# BT_IMU_2_0.net
KiCad netlist of a schematic drawn in EAGLE
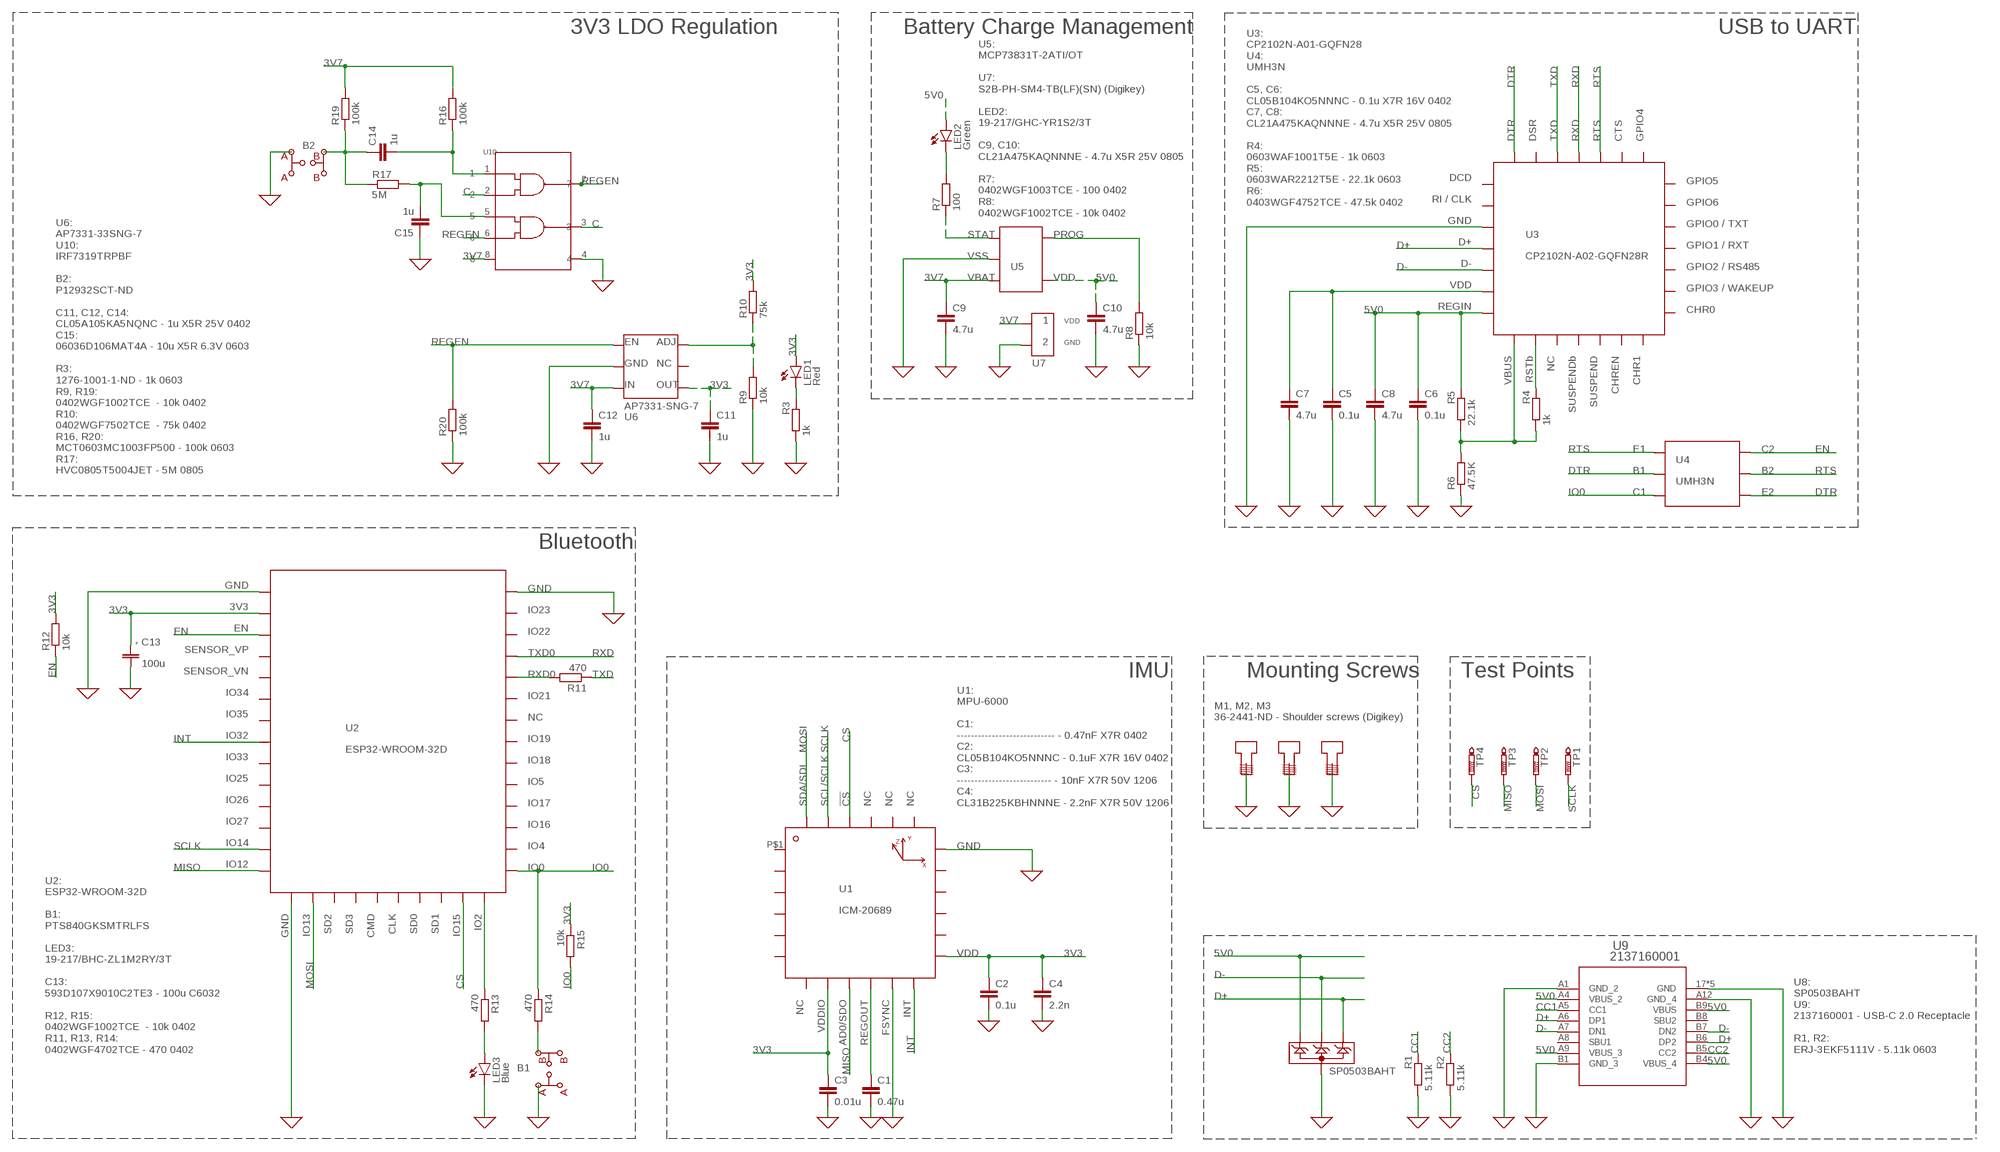
[diagram p0: schematic, sheet 1]

(export (version "E")
  (design (tool "Eeschema 10.0.6"))
  (components
    (comp (ref "B1")
      (value "P12932SCT-ND")
      (footprint "eagle-import:P12932SCT-ND")
      (libsource (lib "eagle-import") (part "P12932SCT-ND"))
    )
    (comp (ref "B2")
      (value "P12932SCT-ND")
      (footprint "eagle-import:P12932SCT-ND")
      (libsource (lib "eagle-import") (part "P12932SCT-ND"))
    )
    (comp (ref "C1")
      (value "0.47u")
      (footprint "eagle-import:C0603")
      (libsource (lib "eagle-import") (part "C-EUC0603"))
    )
    (comp (ref "C2")
      (value "0.1u")
      (footprint "eagle-import:C0402")
      (libsource (lib "eagle-import") (part "C-EUC0402"))
    )
    (comp (ref "C3")
      (value "0.01u")
      (footprint "eagle-import:C0402")
      (libsource (lib "eagle-import") (part "C-EUC0402"))
    )
    (comp (ref "C4")
      (value "2.2n")
      (footprint "eagle-import:C1206")
      (libsource (lib "eagle-import") (part "C-EUC1206"))
    )
    (comp (ref "C5")
      (value "0.1u")
      (footprint "eagle-import:C0402")
      (libsource (lib "eagle-import") (part "C-EUC0402"))
    )
    (comp (ref "C6")
      (value "0.1u")
      (footprint "eagle-import:C0402")
      (libsource (lib "eagle-import") (part "C-EUC0402"))
    )
    (comp (ref "C7")
      (value "4.7u")
      (footprint "eagle-import:C0805")
      (libsource (lib "eagle-import") (part "C-EUC0805"))
    )
    (comp (ref "C8")
      (value "4.7u")
      (footprint "eagle-import:C0805")
      (libsource (lib "eagle-import") (part "C-EUC0805"))
    )
    (comp (ref "C9")
      (value "4.7u")
      (footprint "eagle-import:C0805")
      (libsource (lib "eagle-import") (part "C-EUC0805"))
    )
    (comp (ref "C10")
      (value "4.7u")
      (footprint "eagle-import:C0805")
      (libsource (lib "eagle-import") (part "C-EUC0805"))
    )
    (comp (ref "C11")
      (value "1u")
      (footprint "eagle-import:C0402")
      (libsource (lib "eagle-import") (part "C-EUC0402"))
    )
    (comp (ref "C12")
      (value "1u")
      (footprint "eagle-import:C0402")
      (libsource (lib "eagle-import") (part "C-EUC0402"))
    )
    (comp (ref "C13")
      (value "100u")
      (footprint "eagle-import:C6032")
      (libsource (lib "eagle-import") (part "593D107X9010C2TE3"))
    )
    (comp (ref "C14")
      (value "1u")
      (footprint "eagle-import:C0402")
      (libsource (lib "eagle-import") (part "C-EUC0402"))
    )
    (comp (ref "C15")
      (value "1u")
      (footprint "eagle-import:C0603")
      (libsource (lib "eagle-import") (part "C-EUC0603"))
    )
    (comp (ref "LED1")
      (value "Red")
      (footprint "eagle-import:CHIP-LED0603")
      (libsource (lib "eagle-import") (part "LEDCHIP-LED0603"))
    )
    (comp (ref "LED2")
      (value "Green")
      (footprint "eagle-import:SML0603")
      (libsource (lib "eagle-import") (part "LEDSML0603"))
    )
    (comp (ref "LED3")
      (value "Blue")
      (footprint "eagle-import:SML0603")
      (libsource (lib "eagle-import") (part "LEDSML0603"))
    )
    (comp (ref "M1")
      (value "2441")
      (footprint "eagle-import:2441")
      (libsource (lib "eagle-import") (part "2441"))
    )
    (comp (ref "M2")
      (value "2441")
      (footprint "eagle-import:2441")
      (libsource (lib "eagle-import") (part "2441"))
    )
    (comp (ref "M3")
      (value "2441")
      (footprint "eagle-import:2441")
      (libsource (lib "eagle-import") (part "2441"))
    )
    (comp (ref "R1")
      (value "5.11k")
      (footprint "eagle-import:R0603")
      (libsource (lib "eagle-import") (part "R-EU_R0603"))
    )
    (comp (ref "R2")
      (value "5.11k")
      (footprint "eagle-import:R0603")
      (libsource (lib "eagle-import") (part "R-EU_R0603"))
    )
    (comp (ref "R3")
      (value "1k")
      (footprint "eagle-import:R0603")
      (libsource (lib "eagle-import") (part "R-EU_R0603"))
    )
    (comp (ref "R4")
      (value "1k")
      (footprint "eagle-import:R0603")
      (libsource (lib "eagle-import") (part "R-EU_R0603"))
    )
    (comp (ref "R5")
      (value "22.1k")
      (footprint "eagle-import:R0603")
      (libsource (lib "eagle-import") (part "R-EU_R0603"))
    )
    (comp (ref "R6")
      (value "47.5K")
      (footprint "eagle-import:R0402")
      (libsource (lib "eagle-import") (part "R-EU_R0402"))
    )
    (comp (ref "R7")
      (value "100")
      (footprint "eagle-import:R0402")
      (libsource (lib "eagle-import") (part "R-EU_R0402"))
    )
    (comp (ref "R8")
      (value "10k")
      (footprint "eagle-import:R0402")
      (libsource (lib "eagle-import") (part "R-EU_R0402"))
    )
    (comp (ref "R9")
      (value "10k")
      (footprint "eagle-import:R0402")
      (libsource (lib "eagle-import") (part "R-EU_R0402"))
    )
    (comp (ref "R10")
      (value "75k")
      (footprint "eagle-import:R0402")
      (libsource (lib "eagle-import") (part "R-EU_R0402"))
    )
    (comp (ref "R11")
      (value "470")
      (footprint "eagle-import:R0402")
      (libsource (lib "eagle-import") (part "R-EU_R0402"))
    )
    (comp (ref "R12")
      (value "10k")
      (footprint "eagle-import:R0402")
      (libsource (lib "eagle-import") (part "R-EU_R0402"))
    )
    (comp (ref "R13")
      (value "470")
      (footprint "eagle-import:R0402")
      (libsource (lib "eagle-import") (part "R-EU_R0402"))
    )
    (comp (ref "R14")
      (value "470")
      (footprint "eagle-import:R0402")
      (libsource (lib "eagle-import") (part "R-EU_R0402"))
    )
    (comp (ref "R15")
      (value "10k")
      (footprint "eagle-import:R0402")
      (libsource (lib "eagle-import") (part "R-EU_R0402"))
    )
    (comp (ref "R16")
      (value "100k")
      (footprint "eagle-import:R0603")
      (libsource (lib "eagle-import") (part "R-EU_R0603"))
    )
    (comp (ref "R17")
      (value "5M")
      (footprint "eagle-import:R0805")
      (libsource (lib "eagle-import") (part "R-EU_R0805"))
    )
    (comp (ref "R19")
      (value "100k")
      (footprint "eagle-import:R0603")
      (libsource (lib "eagle-import") (part "R-EU_R0603"))
    )
    (comp (ref "R20")
      (value "100k")
      (footprint "eagle-import:R0603")
      (libsource (lib "eagle-import") (part "R-EU_R0603"))
    )
    (comp (ref "TP1")
      (value "PTR1B1,27")
      (footprint "eagle-import:B1,27")
      (libsource (lib "eagle-import") (part "PTR1B1,27"))
    )
    (comp (ref "TP2")
      (value "PTR1B1,27")
      (footprint "eagle-import:B1,27")
      (libsource (lib "eagle-import") (part "PTR1B1,27"))
    )
    (comp (ref "TP3")
      (value "PTR1B1,27")
      (footprint "eagle-import:B1,27")
      (libsource (lib "eagle-import") (part "PTR1B1,27"))
    )
    (comp (ref "TP4")
      (value "PTR1B1,27")
      (footprint "eagle-import:B1,27")
      (libsource (lib "eagle-import") (part "PTR1B1,27"))
    )
    (comp (ref "U1")
      (value "ICM-20689")
      (footprint "eagle-import:24-QFN(4X4)")
      (libsource (lib "eagle-import") (part "ICM-20689"))
    )
    (comp (ref "U2")
      (value "ESP32-WROOM-32D")
      (footprint "eagle-import:ESP32-WROOM-32D")
      (libsource (lib "eagle-import") (part "ESP32-WROOM-32D"))
    )
    (comp (ref "U3")
      (value "CP2102N-A02-GQFN28R")
      (footprint "eagle-import:28-QFN(5X5)")
      (libsource (lib "eagle-import") (part "CP2102N-A02-GQFN28R"))
    )
    (comp (ref "U4")
      (value "UMH3N")
      (footprint "eagle-import:UMT6")
      (libsource (lib "eagle-import") (part "UMH3N"))
    )
    (comp (ref "U5")
      (value "MCP73831T-2ATI/OT")
      (footprint "eagle-import:SOT-23-5")
      (libsource (lib "eagle-import") (part "MCP73831T-2ATI/OT"))
    )
    (comp (ref "U6")
      (value "AP7331-SNG-7")
      (footprint "eagle-import:U-DFN2020-6")
      (libsource (lib "eagle-import") (part "AP7331-SNG-7"))
    )
    (comp (ref "U7")
      (value "S2B-PH-SM4-TB(LF)(SN)")
      (footprint "eagle-import:S2B-PH-SM4-TB(LF)(SN)")
      (libsource (lib "eagle-import") (part "S2B-PH-SM4-TB(LF)(SN)"))
    )
    (comp (ref "U8")
      (value "SP0503BAHT")
      (footprint "eagle-import:SOT-143-4")
      (libsource (lib "eagle-import") (part "SP0503BAHT"))
    )
    (comp (ref "U9")
      (value "2137160001")
      (footprint "eagle-import:2137160001_MOL")
      (fields (field (name "COPYRIGHT") "Copyright (C) 2018 Accelerated Designs. All rights reserved"))
      (libsource (lib "eagle-import") (part "2137160001"))
    )
    (comp (ref "U10")
      (value "TC7WZ00FKSOT-765")
      (footprint "eagle-import:SOT-765")
      (libsource (lib "eagle-import") (part "TC7WZ00FKSOT-765"))
    )
  )
  (nets
    (net (code "1") (name "/3V3") (class "Default")
      (node (ref "C11") (pin "1") (pinfunction "1_1") (pintype "passive"))
      (node (ref "C13") (pin "P$1") (pinfunction "P$1_P$1") (pintype "bidirectional"))
      (node (ref "C2") (pin "1") (pinfunction "1_1") (pintype "passive"))
      (node (ref "C3") (pin "1") (pinfunction "1_1") (pintype "passive"))
      (node (ref "C4") (pin "1") (pinfunction "1_1") (pintype "passive"))
      (node (ref "LED1") (pin "A") (pinfunction "A_A") (pintype "passive"))
      (node (ref "R10") (pin "2") (pinfunction "2_2") (pintype "passive"))
      (node (ref "R12") (pin "2") (pinfunction "2_2") (pintype "passive"))
      (node (ref "R15") (pin "1") (pinfunction "1_1") (pintype "passive"))
      (node (ref "U1") (pin "P$13") (pinfunction "P$13_P$13") (pintype "power_in"))
      (node (ref "U1") (pin "P$8") (pinfunction "P$8_P$8") (pintype "power_in"))
      (node (ref "U2") (pin "P$2") (pinfunction "P$2_P$2") (pintype "input"))
      (node (ref "U6") (pin "P$4") (pinfunction "P$4_P$4") (pintype "output"))
    )
    (net (code "2") (name "/3V7") (class "Default")
      (node (ref "C12") (pin "1") (pinfunction "1_1") (pintype "passive"))
      (node (ref "C9") (pin "1") (pinfunction "1_1") (pintype "passive"))
      (node (ref "R16") (pin "2") (pinfunction "2_2") (pintype "passive"))
      (node (ref "R19") (pin "2") (pinfunction "2_2") (pintype "passive"))
      (node (ref "U10") (pin "8") (pinfunction "8_8") (pintype "passive"))
      (node (ref "U5") (pin "P$3") (pinfunction "P$3_P$3") (pintype "power_in"))
      (node (ref "U6") (pin "P$3") (pinfunction "P$3_P$3") (pintype "input"))
      (node (ref "U7") (pin "P$1") (pinfunction "P$1_P$1") (pintype "bidirectional"))
    )
    (net (code "3") (name "/5V0") (class "Default")
      (node (ref "C10") (pin "1") (pinfunction "1_1") (pintype "passive"))
      (node (ref "C6") (pin "1") (pinfunction "1_1") (pintype "passive"))
      (node (ref "C8") (pin "1") (pinfunction "1_1") (pintype "passive"))
      (node (ref "LED2") (pin "A") (pinfunction "A_A") (pintype "passive"))
      (node (ref "R5") (pin "2") (pinfunction "2_2") (pintype "passive"))
      (node (ref "U3") (pin "P$6") (pinfunction "P$7_P$6") (pintype "power_in"))
      (node (ref "U5") (pin "P$4") (pinfunction "P$4_P$4") (pintype "power_in"))
      (node (ref "U8") (pin "P$2") (pinfunction "P$2_P$2") (pintype "bidirectional"))
      (node (ref "U9") (pin "A4") (pinfunction "VBUS_2_A4") (pintype "power_in"))
      (node (ref "U9") (pin "A9") (pinfunction "VBUS_3_A9") (pintype "power_in"))
      (node (ref "U9") (pin "B4") (pinfunction "VBUS_4_B4") (pintype "power_in"))
      (node (ref "U9") (pin "B9") (pinfunction "VBUS_B9") (pintype "power_in"))
    )
    (net (code "4") (name "/C") (class "Default")
      (node (ref "U10") (pin "2") (pinfunction "2_2") (pintype "passive"))
      (node (ref "U10") (pin "3") (pinfunction "3_3") (pintype "passive"))
    )
    (net (code "5") (name "/CC1") (class "Default")
      (node (ref "R1") (pin "2") (pinfunction "2_2") (pintype "passive"))
      (node (ref "U9") (pin "A5") (pinfunction "CC1_A5") (pintype "bidirectional"))
    )
    (net (code "6") (name "/CC2") (class "Default")
      (node (ref "R2") (pin "2") (pinfunction "2_2") (pintype "passive"))
      (node (ref "U9") (pin "B5") (pinfunction "CC2_B5") (pintype "bidirectional"))
    )
    (net (code "7") (name "/CS") (class "Default")
      (node (ref "TP4") (pin "TP") (pinfunction "TP_TP") (pintype "input"))
      (node (ref "U1") (pin "P$22") (pinfunction "P$22_P$22") (pintype "input"))
      (node (ref "U2") (pin "P$23") (pinfunction "P$23_P$23") (pintype "input"))
    )
    (net (code "8") (name "/D+") (class "Default")
      (node (ref "U3") (pin "P$3") (pinfunction "P$4_P$3") (pintype "bidirectional"))
      (node (ref "U8") (pin "P$4") (pinfunction "P$4_P$4") (pintype "bidirectional"))
      (node (ref "U9") (pin "A6") (pinfunction "DP1_A6") (pintype "bidirectional"))
      (node (ref "U9") (pin "B6") (pinfunction "DP2_B6") (pintype "bidirectional"))
    )
    (net (code "9") (name "/D-") (class "Default")
      (node (ref "U3") (pin "P$4") (pinfunction "P$5_P$4") (pintype "bidirectional"))
      (node (ref "U8") (pin "P$3") (pinfunction "P$3_P$3") (pintype "bidirectional"))
      (node (ref "U9") (pin "A7") (pinfunction "DN1_A7") (pintype "bidirectional"))
      (node (ref "U9") (pin "B7") (pinfunction "DN2_B7") (pintype "bidirectional"))
    )
    (net (code "10") (name "/DTR") (class "Default")
      (node (ref "U3") (pin "P$27") (pinfunction "P$28_P$27") (pintype "output"))
      (node (ref "U4") (pin "P$2") (pinfunction "P$2_P$2") (pintype "bidirectional"))
      (node (ref "U4") (pin "P$4") (pinfunction "P$4_P$4") (pintype "bidirectional"))
    )
    (net (code "11") (name "/EN") (class "Default")
      (node (ref "R12") (pin "1") (pinfunction "1_1") (pintype "passive"))
      (node (ref "U2") (pin "P$3") (pinfunction "P$3_P$3") (pintype "input"))
      (node (ref "U4") (pin "P$6") (pinfunction "P$6_P$6") (pintype "bidirectional"))
    )
    (net (code "12") (name "/INT") (class "Default")
      (node (ref "U1") (pin "P$12") (pinfunction "P$12_P$12") (pintype "output"))
      (node (ref "U2") (pin "P$8") (pinfunction "P$8_P$8") (pintype "input"))
    )
    (net (code "13") (name "/IO0") (class "Default")
      (node (ref "R14") (pin "1") (pinfunction "1_1") (pintype "passive"))
      (node (ref "R15") (pin "2") (pinfunction "2_2") (pintype "passive"))
      (node (ref "U2") (pin "P$25") (pinfunction "P$25_P$25") (pintype "input"))
      (node (ref "U4") (pin "P$3") (pinfunction "P$3_P$3") (pintype "bidirectional"))
    )
    (net (code "14") (name "/MISO") (class "Default")
      (node (ref "TP3") (pin "TP") (pinfunction "TP_TP") (pintype "input"))
      (node (ref "U1") (pin "P$9") (pinfunction "P$9_P$9") (pintype "input"))
      (node (ref "U2") (pin "P$14") (pinfunction "P$14_P$14") (pintype "input"))
    )
    (net (code "15") (name "/MOSI") (class "Default")
      (node (ref "TP2") (pin "TP") (pinfunction "TP_TP") (pintype "input"))
      (node (ref "U1") (pin "P$24") (pinfunction "P$24_P$24") (pintype "bidirectional"))
      (node (ref "U2") (pin "P$16") (pinfunction "P$16_P$16") (pintype "input"))
    )
    (net (code "16") (name "/REGEN") (class "Default")
      (node (ref "R20") (pin "2") (pinfunction "2_2") (pintype "passive"))
      (node (ref "U10") (pin "6") (pinfunction "6_6") (pintype "passive"))
      (node (ref "U10") (pin "7") (pinfunction "7_7") (pintype "passive"))
      (node (ref "U6") (pin "P$1") (pinfunction "P$1_P$1") (pintype "input"))
    )
    (net (code "17") (name "/RTS") (class "Default")
      (node (ref "U3") (pin "P$23") (pinfunction "P$24_P$23") (pintype "output"))
      (node (ref "U4") (pin "P$1") (pinfunction "P$1_P$1") (pintype "bidirectional"))
      (node (ref "U4") (pin "P$5") (pinfunction "P$5_P$5") (pintype "bidirectional"))
    )
    (net (code "18") (name "/RXD") (class "Default")
      (node (ref "U2") (pin "P$35") (pinfunction "P$35_P$35") (pintype "input"))
      (node (ref "U3") (pin "P$24") (pinfunction "P$25_P$24") (pintype "input"))
    )
    (net (code "19") (name "/SCLK") (class "Default")
      (node (ref "TP1") (pin "TP") (pinfunction "TP_TP") (pintype "input"))
      (node (ref "U1") (pin "P$23") (pinfunction "P$23_P$23") (pintype "input"))
      (node (ref "U2") (pin "P$13") (pinfunction "P$13_P$13") (pintype "input"))
    )
    (net (code "20") (name "/TXD") (class "Default")
      (node (ref "R11") (pin "1") (pinfunction "1_1") (pintype "passive"))
      (node (ref "U3") (pin "P$25") (pinfunction "P$26_P$25") (pintype "output"))
    )
    (net (code "21") (name "GND") (class "Default")
      (node (ref "B1") (pin "P$2") (pinfunction "P$2_P$2") (pintype "bidirectional"))
      (node (ref "B2") (pin "P$2") (pinfunction "P$2_P$2") (pintype "bidirectional"))
      (node (ref "C1") (pin "2") (pinfunction "2_2") (pintype "passive"))
      (node (ref "C10") (pin "2") (pinfunction "2_2") (pintype "passive"))
      (node (ref "C11") (pin "2") (pinfunction "2_2") (pintype "passive"))
      (node (ref "C12") (pin "2") (pinfunction "2_2") (pintype "passive"))
      (node (ref "C13") (pin "P$2") (pinfunction "P$2_P$2") (pintype "bidirectional"))
      (node (ref "C15") (pin "1") (pinfunction "1_1") (pintype "passive"))
      (node (ref "C2") (pin "2") (pinfunction "2_2") (pintype "passive"))
      (node (ref "C3") (pin "2") (pinfunction "2_2") (pintype "passive"))
      (node (ref "C4") (pin "2") (pinfunction "2_2") (pintype "passive"))
      (node (ref "C5") (pin "2") (pinfunction "2_2") (pintype "passive"))
      (node (ref "C6") (pin "2") (pinfunction "2_2") (pintype "passive"))
      (node (ref "C7") (pin "2") (pinfunction "2_2") (pintype "passive"))
      (node (ref "C8") (pin "2") (pinfunction "2_2") (pintype "passive"))
      (node (ref "C9") (pin "2") (pinfunction "2_2") (pintype "passive"))
      (node (ref "LED3") (pin "C") (pinfunction "C_C") (pintype "passive"))
      (node (ref "M1") (pin "P$1") (pinfunction "P$1_P$1") (pintype "power_in"))
      (node (ref "M2") (pin "P$1") (pinfunction "P$1_P$1") (pintype "power_in"))
      (node (ref "M3") (pin "P$1") (pinfunction "P$1_P$1") (pintype "power_in"))
      (node (ref "R1") (pin "1") (pinfunction "1_1") (pintype "passive"))
      (node (ref "R2") (pin "1") (pinfunction "1_1") (pintype "passive"))
      (node (ref "R20") (pin "1") (pinfunction "1_1") (pintype "passive"))
      (node (ref "R3") (pin "1") (pinfunction "1_1") (pintype "passive"))
      (node (ref "R6") (pin "1") (pinfunction "1_1") (pintype "passive"))
      (node (ref "R8") (pin "1") (pinfunction "1_1") (pintype "passive"))
      (node (ref "R9") (pin "1") (pinfunction "1_1") (pintype "passive"))
      (node (ref "U1") (pin "P$11") (pinfunction "P$11_P$11") (pintype "input"))
      (node (ref "U1") (pin "P$18") (pinfunction "P$18_P$18") (pintype "power_in"))
      (node (ref "U10") (pin "4") (pinfunction "4_4") (pintype "passive"))
      (node (ref "U2") (pin "P$1") (pinfunction "P$1_P$1") (pintype "input"))
      (node (ref "U2") (pin "P$15") (pinfunction "P$15_P$15") (pintype "input"))
      (node (ref "U2") (pin "P$38") (pinfunction "P$38_P$38") (pintype "input"))
      (node (ref "U2") (pin "P$39") (pinfunction "P$1_P$39") (pintype "input"))
      (node (ref "U2") (pin "P$40") (pinfunction "P$1_P$40") (pintype "input"))
      (node (ref "U2") (pin "P$41") (pinfunction "P$1_P$41") (pintype "input"))
      (node (ref "U2") (pin "P$42") (pinfunction "P$1_P$42") (pintype "input"))
      (node (ref "U2") (pin "P$43") (pinfunction "P$1_P$43") (pintype "input"))
      (node (ref "U2") (pin "P$44") (pinfunction "P$1_P$44") (pintype "input"))
      (node (ref "U2") (pin "P$45") (pinfunction "P$1_P$45") (pintype "input"))
      (node (ref "U2") (pin "P$46") (pinfunction "P$1_P$46") (pintype "input"))
      (node (ref "U2") (pin "P$47") (pinfunction "P$1_P$47") (pintype "input"))
      (node (ref "U3") (pin "P$2") (pinfunction "P$3_P$2") (pintype "power_in"))
      (node (ref "U3") (pin "P$28") (pinfunction "P$3_P$28") (pintype "power_in"))
      (node (ref "U3") (pin "P$29") (pinfunction "P$3_P$29") (pintype "power_in"))
      (node (ref "U3") (pin "P$30") (pinfunction "P$3_P$30") (pintype "power_in"))
      (node (ref "U3") (pin "P$31") (pinfunction "P$3_P$31") (pintype "power_in"))
      (node (ref "U3") (pin "P$32") (pinfunction "P$3_P$32") (pintype "power_in"))
      (node (ref "U3") (pin "P$33") (pinfunction "P$3_P$33") (pintype "power_in"))
      (node (ref "U3") (pin "P$34") (pinfunction "P$3_P$34") (pintype "power_in"))
      (node (ref "U3") (pin "P$35") (pinfunction "P$3_P$35") (pintype "power_in"))
      (node (ref "U3") (pin "P$36") (pinfunction "P$3_P$36") (pintype "power_in"))
      (node (ref "U5") (pin "P$2") (pinfunction "P$2_P$2") (pintype "power_in"))
      (node (ref "U6") (pin "P$2") (pinfunction "P$2_P$2") (pintype "power_in"))
      (node (ref "U6") (pin "P$7") (pinfunction "P$2_P$7") (pintype "power_in"))
      (node (ref "U6") (pin "P$8") (pinfunction "P$2_P$8") (pintype "power_in"))
      (node (ref "U7") (pin "P$2") (pinfunction "P$2_P$2") (pintype "bidirectional"))
      (node (ref "U8") (pin "P$1") (pinfunction "P$1_P$1") (pintype "bidirectional"))
      (node (ref "U9") (pin "17") (pinfunction "GND_17") (pintype "passive"))
      (node (ref "U9") (pin "18") (pinfunction "GND_18") (pintype "passive"))
      (node (ref "U9") (pin "19") (pinfunction "GND_19") (pintype "passive"))
      (node (ref "U9") (pin "20") (pinfunction "GND_20") (pintype "passive"))
      (node (ref "U9") (pin "A1") (pinfunction "GND_2_A1") (pintype "passive"))
      (node (ref "U9") (pin "A12") (pinfunction "GND_4_A12") (pintype "passive"))
      (node (ref "U9") (pin "B1") (pinfunction "GND_3_B1") (pintype "passive"))
      (node (ref "U9") (pin "B12") (pinfunction "GND_B12") (pintype "passive"))
    )
    (net (code "22") (name "Net-(B1-PadP$4)") (class "Default")
      (node (ref "B1") (pin "P$4") (pinfunction "P$4_P$4") (pintype "bidirectional"))
      (node (ref "R14") (pin "2") (pinfunction "2_2") (pintype "passive"))
    )
    (net (code "23") (name "Net-(B2-PadP$4)") (class "Default")
      (node (ref "B2") (pin "P$4") (pinfunction "P$4_P$4") (pintype "bidirectional"))
      (node (ref "C14") (pin "1") (pinfunction "1_1") (pintype "passive"))
      (node (ref "R17") (pin "1") (pinfunction "1_1") (pintype "passive"))
      (node (ref "R19") (pin "1") (pinfunction "1_1") (pintype "passive"))
    )
    (net (code "24") (name "Net-(C1-Pad1)") (class "Default")
      (node (ref "C1") (pin "1") (pinfunction "1_1") (pintype "passive"))
      (node (ref "U1") (pin "P$10") (pinfunction "P$10_P$10") (pintype "power_in"))
    )
    (net (code "25") (name "Net-(C14-Pad2)") (class "Default")
      (node (ref "C14") (pin "2") (pinfunction "2_2") (pintype "passive"))
      (node (ref "R16") (pin "1") (pinfunction "1_1") (pintype "passive"))
      (node (ref "U10") (pin "1") (pinfunction "1_1") (pintype "passive"))
    )
    (net (code "26") (name "Net-(C15-Pad2)") (class "Default")
      (node (ref "C15") (pin "2") (pinfunction "2_2") (pintype "passive"))
      (node (ref "R17") (pin "2") (pinfunction "2_2") (pintype "passive"))
      (node (ref "U10") (pin "5") (pinfunction "5_5") (pintype "passive"))
    )
    (net (code "27") (name "Net-(LED1-PadC)") (class "Default")
      (node (ref "LED1") (pin "C") (pinfunction "C_C") (pintype "passive"))
      (node (ref "R3") (pin "2") (pinfunction "2_2") (pintype "passive"))
    )
    (net (code "28") (name "Net-(LED2-PadC)") (class "Default")
      (node (ref "LED2") (pin "C") (pinfunction "C_C") (pintype "passive"))
      (node (ref "R7") (pin "2") (pinfunction "2_2") (pintype "passive"))
    )
    (net (code "29") (name "Net-(LED3-PadA)") (class "Default")
      (node (ref "LED3") (pin "A") (pinfunction "A_A") (pintype "passive"))
      (node (ref "R13") (pin "2") (pinfunction "2_2") (pintype "passive"))
    )
    (net (code "30") (name "Net-(R7-Pad1)") (class "Default")
      (node (ref "R7") (pin "1") (pinfunction "1_1") (pintype "passive"))
      (node (ref "U5") (pin "P$1") (pinfunction "P$1_P$1") (pintype "bidirectional"))
    )
    (net (code "31") (name "Net-(R8-Pad2)") (class "Default")
      (node (ref "R8") (pin "2") (pinfunction "2_2") (pintype "passive"))
      (node (ref "U5") (pin "P$5") (pinfunction "P$5_P$5") (pintype "input"))
    )
    (net (code "32") (name "Net-(R10-Pad1)") (class "Default")
      (node (ref "R10") (pin "1") (pinfunction "1_1") (pintype "passive"))
      (node (ref "R9") (pin "2") (pinfunction "2_2") (pintype "passive"))
      (node (ref "U6") (pin "P$6") (pinfunction "P$6_P$6") (pintype "input"))
    )
    (net (code "33") (name "Net-(R11-Pad2)") (class "Default")
      (node (ref "R11") (pin "2") (pinfunction "2_2") (pintype "passive"))
      (node (ref "U2") (pin "P$34") (pinfunction "P$34_P$34") (pintype "input"))
    )
    (net (code "34") (name "Net-(R13-Pad1)") (class "Default")
      (node (ref "R13") (pin "1") (pinfunction "1_1") (pintype "passive"))
      (node (ref "U2") (pin "P$24") (pinfunction "P$24_P$24") (pintype "input"))
    )
    (net (code "35") (name "Net-(U3-P$6)") (class "Default")
      (node (ref "C5") (pin "1") (pinfunction "1_1") (pintype "passive"))
      (node (ref "C7") (pin "1") (pinfunction "1_1") (pintype "passive"))
      (node (ref "U3") (pin "P$5") (pinfunction "P$6_P$5") (pintype "power_in"))
    )
    (net (code "36") (name "Net-(U3-P$8)") (class "Default")
      (node (ref "R4") (pin "1") (pinfunction "1_1") (pintype "passive"))
      (node (ref "R5") (pin "1") (pinfunction "1_1") (pintype "passive"))
      (node (ref "R6") (pin "2") (pinfunction "2_2") (pintype "passive"))
      (node (ref "U3") (pin "P$7") (pinfunction "P$8_P$7") (pintype "input"))
    )
    (net (code "37") (name "Net-(U3-P$9)") (class "Default")
      (node (ref "R4") (pin "2") (pinfunction "2_2") (pintype "passive"))
      (node (ref "U3") (pin "P$8") (pinfunction "P$9_P$8") (pintype "input"))
    )
    (net (code "38") (name "unconnected-(B1-PadP$1)") (class "Default")
      (node (ref "B1") (pin "P$1") (pinfunction "P$1_P$1") (pintype "bidirectional"))
    )
    (net (code "39") (name "unconnected-(B1-PadP$3)") (class "Default")
      (node (ref "B1") (pin "P$3") (pinfunction "P$3_P$3") (pintype "bidirectional"))
    )
    (net (code "40") (name "unconnected-(B2-PadP$1)") (class "Default")
      (node (ref "B2") (pin "P$1") (pinfunction "P$1_P$1") (pintype "bidirectional"))
    )
    (net (code "41") (name "unconnected-(B2-PadP$3)") (class "Default")
      (node (ref "B2") (pin "P$3") (pinfunction "P$3_P$3") (pintype "bidirectional"))
    )
    (net (code "42") (name "unconnected-(U1-PadP$1)") (class "Default")
      (node (ref "U1") (pin "P$1") (pinfunction "P$1_P$1") (pintype "no_connect"))
    )
    (net (code "43") (name "unconnected-(U1-PadP$2)") (class "Default")
      (node (ref "U1") (pin "P$2") (pinfunction "P$2_P$2") (pintype "no_connect"))
    )
    (net (code "44") (name "unconnected-(U1-PadP$3)") (class "Default")
      (node (ref "U1") (pin "P$3") (pinfunction "P$3_P$3") (pintype "no_connect"))
    )
    (net (code "45") (name "unconnected-(U1-PadP$4)") (class "Default")
      (node (ref "U1") (pin "P$4") (pinfunction "P$4_P$4") (pintype "no_connect"))
    )
    (net (code "46") (name "unconnected-(U1-PadP$5)") (class "Default")
      (node (ref "U1") (pin "P$5") (pinfunction "P$5_P$5") (pintype "no_connect"))
    )
    (net (code "47") (name "unconnected-(U1-PadP$6)") (class "Default")
      (node (ref "U1") (pin "P$6") (pinfunction "P$6_P$6") (pintype "no_connect"))
    )
    (net (code "48") (name "unconnected-(U1-PadP$7)") (class "Default")
      (node (ref "U1") (pin "P$7") (pinfunction "P$7_P$7") (pintype "no_connect"))
    )
    (net (code "49") (name "unconnected-(U1-PadP$14)") (class "Default")
      (node (ref "U1") (pin "P$14") (pinfunction "P$14_P$14") (pintype "no_connect"))
    )
    (net (code "50") (name "unconnected-(U1-PadP$15)") (class "Default")
      (node (ref "U1") (pin "P$15") (pinfunction "P$15_P$15") (pintype "no_connect"))
    )
    (net (code "51") (name "unconnected-(U1-PadP$16)") (class "Default")
      (node (ref "U1") (pin "P$16") (pinfunction "P$16_P$16") (pintype "no_connect"))
    )
    (net (code "52") (name "unconnected-(U1-PadP$17)") (class "Default")
      (node (ref "U1") (pin "P$17") (pinfunction "P$17_P$17") (pintype "no_connect"))
    )
    (net (code "53") (name "unconnected-(U1-PadP$19)") (class "Default")
      (node (ref "U1") (pin "P$19") (pinfunction "P$19_P$19") (pintype "no_connect"))
    )
    (net (code "54") (name "unconnected-(U1-PadP$20)") (class "Default")
      (node (ref "U1") (pin "P$20") (pinfunction "P$20_P$20") (pintype "no_connect"))
    )
    (net (code "55") (name "unconnected-(U1-PadP$21)") (class "Default")
      (node (ref "U1") (pin "P$21") (pinfunction "P$21_P$21") (pintype "no_connect"))
    )
    (net (code "56") (name "unconnected-(U2-PadP$4)") (class "Default")
      (node (ref "U2") (pin "P$4") (pinfunction "P$4_P$4") (pintype "input"))
    )
    (net (code "57") (name "unconnected-(U2-PadP$5)") (class "Default")
      (node (ref "U2") (pin "P$5") (pinfunction "P$5_P$5") (pintype "input"))
    )
    (net (code "58") (name "unconnected-(U2-PadP$6)") (class "Default")
      (node (ref "U2") (pin "P$6") (pinfunction "P$6_P$6") (pintype "input"))
    )
    (net (code "59") (name "unconnected-(U2-PadP$7)") (class "Default")
      (node (ref "U2") (pin "P$7") (pinfunction "P$7_P$7") (pintype "input"))
    )
    (net (code "60") (name "unconnected-(U2-PadP$9)") (class "Default")
      (node (ref "U2") (pin "P$9") (pinfunction "P$9_P$9") (pintype "input"))
    )
    (net (code "61") (name "unconnected-(U2-PadP$10)") (class "Default")
      (node (ref "U2") (pin "P$10") (pinfunction "P$10_P$10") (pintype "input"))
    )
    (net (code "62") (name "unconnected-(U2-PadP$11)") (class "Default")
      (node (ref "U2") (pin "P$11") (pinfunction "P$11_P$11") (pintype "input"))
    )
    (net (code "63") (name "unconnected-(U2-PadP$12)") (class "Default")
      (node (ref "U2") (pin "P$12") (pinfunction "P$12_P$12") (pintype "input"))
    )
    (net (code "64") (name "unconnected-(U2-PadP$17)") (class "Default")
      (node (ref "U2") (pin "P$17") (pinfunction "P$17_P$17") (pintype "input"))
    )
    (net (code "65") (name "unconnected-(U2-PadP$18)") (class "Default")
      (node (ref "U2") (pin "P$18") (pinfunction "P$18_P$18") (pintype "input"))
    )
    (net (code "66") (name "unconnected-(U2-PadP$19)") (class "Default")
      (node (ref "U2") (pin "P$19") (pinfunction "P$19_P$19") (pintype "input"))
    )
    (net (code "67") (name "unconnected-(U2-PadP$20)") (class "Default")
      (node (ref "U2") (pin "P$20") (pinfunction "P$20_P$20") (pintype "input"))
    )
    (net (code "68") (name "unconnected-(U2-PadP$21)") (class "Default")
      (node (ref "U2") (pin "P$21") (pinfunction "P$21_P$21") (pintype "input"))
    )
    (net (code "69") (name "unconnected-(U2-PadP$22)") (class "Default")
      (node (ref "U2") (pin "P$22") (pinfunction "P$22_P$22") (pintype "input"))
    )
    (net (code "70") (name "unconnected-(U2-PadP$26)") (class "Default")
      (node (ref "U2") (pin "P$26") (pinfunction "P$26_P$26") (pintype "input"))
    )
    (net (code "71") (name "unconnected-(U2-PadP$27)") (class "Default")
      (node (ref "U2") (pin "P$27") (pinfunction "P$27_P$27") (pintype "input"))
    )
    (net (code "72") (name "unconnected-(U2-PadP$28)") (class "Default")
      (node (ref "U2") (pin "P$28") (pinfunction "P$28_P$28") (pintype "input"))
    )
    (net (code "73") (name "unconnected-(U2-PadP$29)") (class "Default")
      (node (ref "U2") (pin "P$29") (pinfunction "P$29_P$29") (pintype "input"))
    )
    (net (code "74") (name "unconnected-(U2-PadP$30)") (class "Default")
      (node (ref "U2") (pin "P$30") (pinfunction "P$30_P$30") (pintype "input"))
    )
    (net (code "75") (name "unconnected-(U2-PadP$31)") (class "Default")
      (node (ref "U2") (pin "P$31") (pinfunction "P$31_P$31") (pintype "input"))
    )
    (net (code "76") (name "unconnected-(U2-PadP$32)") (class "Default")
      (node (ref "U2") (pin "P$32") (pinfunction "P$32_P$32") (pintype "input"))
    )
    (net (code "77") (name "unconnected-(U2-PadP$33)") (class "Default")
      (node (ref "U2") (pin "P$33") (pinfunction "P$33_P$33") (pintype "input"))
    )
    (net (code "78") (name "unconnected-(U2-PadP$36)") (class "Default")
      (node (ref "U2") (pin "P$36") (pinfunction "P$36_P$36") (pintype "input"))
    )
    (net (code "79") (name "unconnected-(U2-PadP$37)") (class "Default")
      (node (ref "U2") (pin "P$37") (pinfunction "P$37_P$37") (pintype "input"))
    )
    (net (code "80") (name "unconnected-(U3-P$1-PadP$0)") (class "Default")
      (node (ref "U3") (pin "P$0") (pinfunction "P$1_P$0") (pintype "input"))
    )
    (net (code "81") (name "unconnected-(U3-P$2-PadP$1)") (class "Default")
      (node (ref "U3") (pin "P$1") (pinfunction "P$2_P$1") (pintype "bidirectional"))
    )
    (net (code "82") (name "unconnected-(U3-P$10-PadP$9)") (class "Default")
      (node (ref "U3") (pin "P$9") (pinfunction "P$10_P$9") (pintype "no_connect"))
    )
    (net (code "83") (name "unconnected-(U3-P$11-PadP$10)") (class "Default")
      (node (ref "U3") (pin "P$10") (pinfunction "P$11_P$10") (pintype "output"))
    )
    (net (code "84") (name "unconnected-(U3-P$12-PadP$11)") (class "Default")
      (node (ref "U3") (pin "P$11") (pinfunction "P$12_P$11") (pintype "output"))
    )
    (net (code "85") (name "unconnected-(U3-P$13-PadP$12)") (class "Default")
      (node (ref "U3") (pin "P$12") (pinfunction "P$13_P$12") (pintype "output"))
    )
    (net (code "86") (name "unconnected-(U3-P$14-PadP$13)") (class "Default")
      (node (ref "U3") (pin "P$13") (pinfunction "P$14_P$13") (pintype "output"))
    )
    (net (code "87") (name "unconnected-(U3-P$15-PadP$14)") (class "Default")
      (node (ref "U3") (pin "P$14") (pinfunction "P$15_P$14") (pintype "output"))
    )
    (net (code "88") (name "unconnected-(U3-P$16-PadP$15)") (class "Default")
      (node (ref "U3") (pin "P$15") (pinfunction "P$16_P$15") (pintype "bidirectional"))
    )
    (net (code "89") (name "unconnected-(U3-P$17-PadP$16)") (class "Default")
      (node (ref "U3") (pin "P$16") (pinfunction "P$17_P$16") (pintype "bidirectional"))
    )
    (net (code "90") (name "unconnected-(U3-P$18-PadP$17)") (class "Default")
      (node (ref "U3") (pin "P$17") (pinfunction "P$18_P$17") (pintype "bidirectional"))
    )
    (net (code "91") (name "unconnected-(U3-P$19-PadP$18)") (class "Default")
      (node (ref "U3") (pin "P$18") (pinfunction "P$19_P$18") (pintype "bidirectional"))
    )
    (net (code "92") (name "unconnected-(U3-P$20-PadP$19)") (class "Default")
      (node (ref "U3") (pin "P$19") (pinfunction "P$20_P$19") (pintype "bidirectional"))
    )
    (net (code "93") (name "unconnected-(U3-P$21-PadP$20)") (class "Default")
      (node (ref "U3") (pin "P$20") (pinfunction "P$21_P$20") (pintype "bidirectional"))
    )
    (net (code "94") (name "unconnected-(U3-P$22-PadP$21)") (class "Default")
      (node (ref "U3") (pin "P$21") (pinfunction "P$22_P$21") (pintype "bidirectional"))
    )
    (net (code "95") (name "unconnected-(U3-P$23-PadP$22)") (class "Default")
      (node (ref "U3") (pin "P$22") (pinfunction "P$23_P$22") (pintype "input"))
    )
    (net (code "96") (name "unconnected-(U3-P$27-PadP$26)") (class "Default")
      (node (ref "U3") (pin "P$26") (pinfunction "P$27_P$26") (pintype "input"))
    )
    (net (code "97") (name "unconnected-(U6-PadP$5)") (class "Default")
      (node (ref "U6") (pin "P$5") (pinfunction "P$5_P$5") (pintype "no_connect"))
    )
    (net (code "98") (name "unconnected-(U9-SBU1-PadA8)") (class "Default")
      (node (ref "U9") (pin "A8") (pinfunction "SBU1_A8") (pintype "bidirectional"))
    )
    (net (code "99") (name "unconnected-(U9-SBU2-PadB8)") (class "Default")
      (node (ref "U9") (pin "B8") (pinfunction "SBU2_B8") (pintype "bidirectional"))
    )
  )
)
